# Data_Acquisition.net
KiCad netlist of a schematic drawn in EAGLE
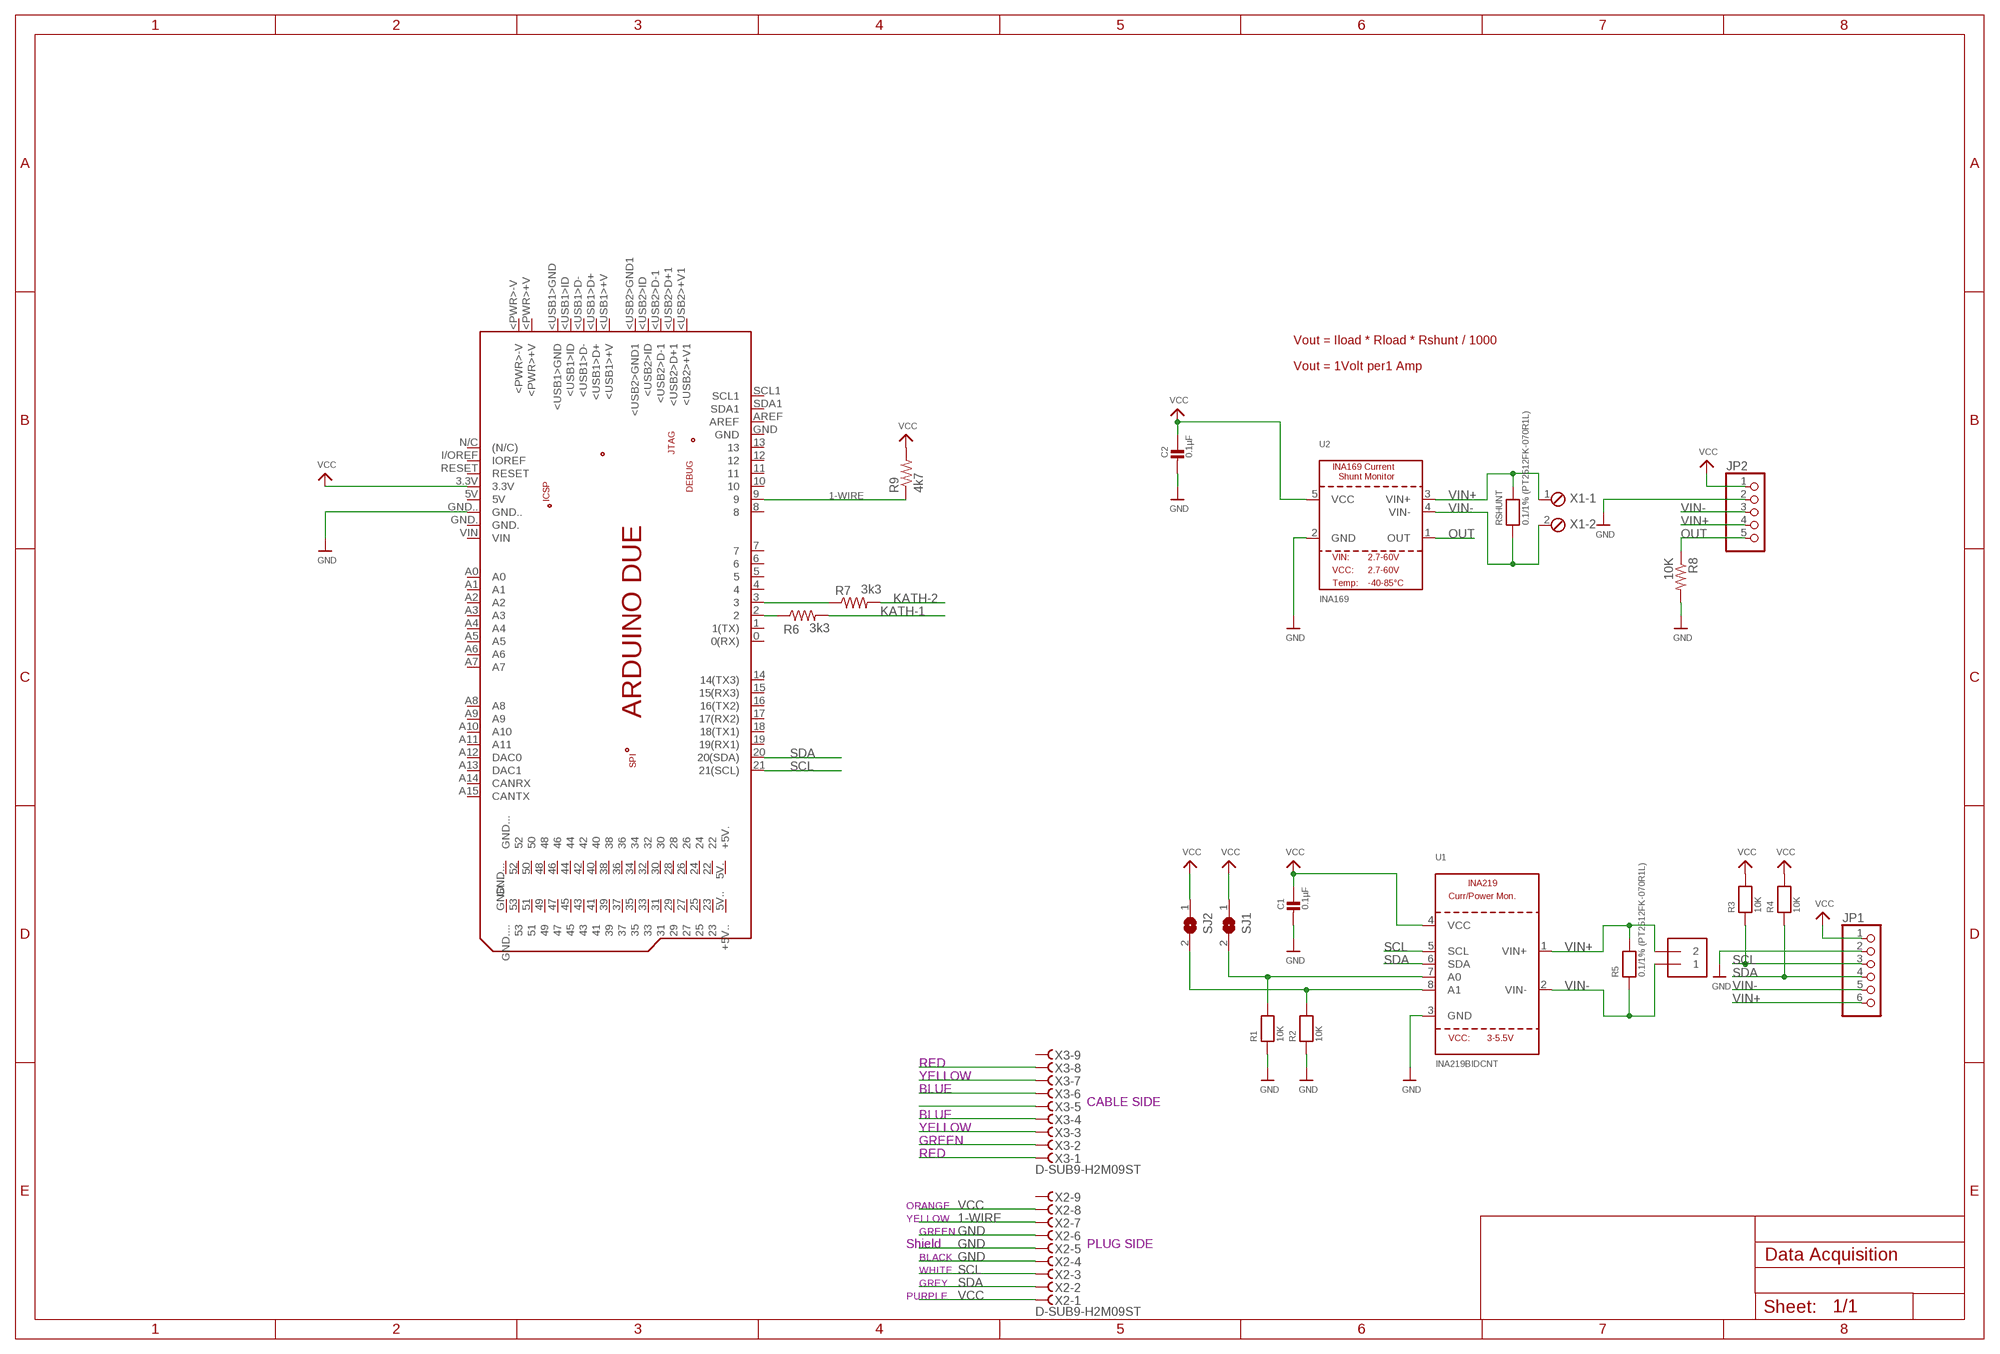
[diagram p0: schematic, sheet 1]

(export (version "E")
  (design (tool "Eeschema 10.0.6"))
  (components
    (comp (ref "C1")
      (value "0.1µF")
      (footprint "eagle-import:0805")
      (libsource (lib "eagle-import") (part "CAP_CERAMIC0805"))
    )
    (comp (ref "C2")
      (value "0.1µF")
      (footprint "eagle-import:0805")
      (libsource (lib "eagle-import") (part "CAP_CERAMIC0805"))
    )
    (comp (ref "J1")
      (value "TERMBLOCK_1X2-3.5MM")
      (footprint "eagle-import:1X2-3.5MM")
      (libsource (lib "eagle-import") (part "TERMBLOCK_1X2-3.5MM"))
    )
    (comp (ref "JP1")
      (value "HEADER-1X670MIL")
      (footprint "eagle-import:1X06_ROUND_70")
      (libsource (lib "eagle-import") (part "HEADER-1X670MIL"))
    )
    (comp (ref "JP2")
      (value "HEADER-1X570MIL")
      (footprint "eagle-import:1X05_ROUND_70")
      (libsource (lib "eagle-import") (part "HEADER-1X570MIL"))
    )
    (comp (ref "PCB1")
      (value "ARDUINO_DUE")
      (footprint "eagle-import:ARDUINO_DUE")
      (libsource (lib "eagle-import") (part "ARDUINO_DUE"))
    )
    (comp (ref "R1")
      (value "10K")
      (footprint "eagle-import:0805")
      (libsource (lib "eagle-import") (part "RESISTOR0805"))
    )
    (comp (ref "R2")
      (value "10K")
      (footprint "eagle-import:0805")
      (libsource (lib "eagle-import") (part "RESISTOR0805"))
    )
    (comp (ref "R3")
      (value "10K")
      (footprint "eagle-import:0805")
      (libsource (lib "eagle-import") (part "RESISTOR0805"))
    )
    (comp (ref "R4")
      (value "10K")
      (footprint "eagle-import:0805")
      (libsource (lib "eagle-import") (part "RESISTOR0805"))
    )
    (comp (ref "R5")
      (value "0.1/1% (PT2512FK-070R1L)")
      (footprint "eagle-import:2512")
      (libsource (lib "eagle-import") (part "RESISTOR2512"))
    )
    (comp (ref "R6")
      (value "3k3")
      (footprint "eagle-import:0204_7")
      (libsource (lib "eagle-import") (part "R-US_0204/7"))
    )
    (comp (ref "R7")
      (value "3k3")
      (footprint "eagle-import:0204_7")
      (libsource (lib "eagle-import") (part "R-US_0204/7"))
    )
    (comp (ref "R8")
      (value "10K")
      (footprint "eagle-import:0805-THM")
      (libsource (lib "eagle-import") (part "RESISTOR_DUAL"))
    )
    (comp (ref "R9")
      (value "4k7")
      (footprint "eagle-import:0207_10")
      (libsource (lib "eagle-import") (part "rcl_334_R-US_0207/10"))
    )
    (comp (ref "RSHUNT")
      (value "0.1/1% (PT2512FK-070R1L)")
      (footprint "eagle-import:2512")
      (libsource (lib "eagle-import") (part "RESISTOR2512"))
    )
    (comp (ref "SJ1")
      (value "SOLDERJUMPERREFLOW_NOPASTE")
      (footprint "eagle-import:SOLDERJUMPER_REFLOW_NOPASTE")
      (libsource (lib "eagle-import") (part "SOLDERJUMPERREFLOW_NOPASTE"))
    )
    (comp (ref "SJ2")
      (value "SOLDERJUMPERREFLOW_NOPASTE")
      (footprint "eagle-import:SOLDERJUMPER_REFLOW_NOPASTE")
      (libsource (lib "eagle-import") (part "SOLDERJUMPERREFLOW_NOPASTE"))
    )
    (comp (ref "U1")
      (value "INA219BIDCNT")
      (footprint "eagle-import:SOT23-8")
      (libsource (lib "eagle-import") (part "INA219"))
    )
    (comp (ref "U2")
      (value "INA169")
      (footprint "eagle-import:SOT23-5")
      (libsource (lib "eagle-import") (part "INA169"))
    )
    (comp (ref "X1")
      (value "MPT2")
      (footprint "eagle-import:2POL254")
      (libsource (lib "eagle-import") (part "MPT2"))
    )
    (comp (ref "X2")
      (value "D-SUB9-H2M09ST")
      (footprint "eagle-import:H2M09ST")
      (libsource (lib "eagle-import") (part "D-SUB9-H2M09ST"))
    )
    (comp (ref "X3")
      (value "D-SUB9-H2M09ST")
      (footprint "eagle-import:H2M09ST")
      (libsource (lib "eagle-import") (part "D-SUB9-H2M09ST"))
    )
  )
  (nets
    (net (code "1") (name "/1-WIRE") (class "Default")
      (node (ref "PCB1") (pin "9") (pinfunction "9_9") (pintype "bidirectional"))
      (node (ref "R9") (pin "1") (pinfunction "1_1") (pintype "passive"))
      (node (ref "X2") (pin "7") (pinfunction "F_7") (pintype "passive"))
    )
    (net (code "2") (name "/KATH-1") (class "Default")
      (node (ref "R6") (pin "2") (pinfunction "2_2") (pintype "passive"))
    )
    (net (code "3") (name "/KATH-2") (class "Default")
      (node (ref "R7") (pin "2") (pinfunction "2_2") (pintype "passive"))
    )
    (net (code "4") (name "/OUT") (class "Default")
      (node (ref "JP2") (pin "5") (pinfunction "5_5") (pintype "passive"))
      (node (ref "R8") (pin "1") (pinfunction "1_1") (pintype "passive"))
      (node (ref "U2") (pin "1") (pinfunction "OUT_1") (pintype "output"))
    )
    (net (code "5") (name "/SCL") (class "Default")
      (node (ref "JP1") (pin "3") (pinfunction "3_3") (pintype "passive"))
      (node (ref "PCB1") (pin "21") (pinfunction "21(SCL)_21") (pintype "bidirectional"))
      (node (ref "R3") (pin "1") (pinfunction "1_1") (pintype "passive"))
      (node (ref "U1") (pin "5") (pinfunction "SCL_5") (pintype "bidirectional"))
      (node (ref "X2") (pin "3") (pinfunction "F_3") (pintype "passive"))
    )
    (net (code "6") (name "/SDA") (class "Default")
      (node (ref "JP1") (pin "4") (pinfunction "4_4") (pintype "passive"))
      (node (ref "PCB1") (pin "20") (pinfunction "20(SDA)_20") (pintype "bidirectional"))
      (node (ref "R4") (pin "1") (pinfunction "1_1") (pintype "passive"))
      (node (ref "U1") (pin "6") (pinfunction "SDA_6") (pintype "bidirectional"))
      (node (ref "X2") (pin "2") (pinfunction "F_2") (pintype "passive"))
    )
    (net (code "7") (name "/VIN+") (class "Default")
      (node (ref "J1") (pin "2") (pinfunction "2_2") (pintype "passive"))
      (node (ref "JP1") (pin "6") (pinfunction "6_6") (pintype "passive"))
      (node (ref "JP2") (pin "4") (pinfunction "4_4") (pintype "passive"))
      (node (ref "R5") (pin "2") (pinfunction "2_2") (pintype "passive"))
      (node (ref "RSHUNT") (pin "2") (pinfunction "2_2") (pintype "passive"))
      (node (ref "U1") (pin "1") (pinfunction "VIN+_1") (pintype "bidirectional"))
      (node (ref "U2") (pin "3") (pinfunction "VIN+_3") (pintype "bidirectional"))
      (node (ref "X1") (pin "1") (pinfunction "1_1") (pintype "passive"))
    )
    (net (code "8") (name "/VIN-") (class "Default")
      (node (ref "J1") (pin "1") (pinfunction "1_1") (pintype "passive"))
      (node (ref "JP1") (pin "5") (pinfunction "5_5") (pintype "passive"))
      (node (ref "JP2") (pin "3") (pinfunction "3_3") (pintype "passive"))
      (node (ref "R5") (pin "1") (pinfunction "1_1") (pintype "passive"))
      (node (ref "RSHUNT") (pin "1") (pinfunction "1_1") (pintype "passive"))
      (node (ref "U1") (pin "2") (pinfunction "VIN-_2") (pintype "bidirectional"))
      (node (ref "U2") (pin "4") (pinfunction "VIN-_4") (pintype "bidirectional"))
      (node (ref "X1") (pin "2") (pinfunction "1_2") (pintype "passive"))
    )
    (net (code "9") (name "GND") (class "Default")
      (node (ref "C1") (pin "2") (pinfunction "2_2") (pintype "passive"))
      (node (ref "C2") (pin "2") (pinfunction "2_2") (pintype "passive"))
      (node (ref "JP1") (pin "2") (pinfunction "2_2") (pintype "passive"))
      (node (ref "JP2") (pin "2") (pinfunction "2_2") (pintype "passive"))
      (node (ref "PCB1") (pin "GND..") (pinfunction "GND.._GND..") (pintype "bidirectional"))
      (node (ref "R1") (pin "1") (pinfunction "1_1") (pintype "passive"))
      (node (ref "R2") (pin "1") (pinfunction "1_1") (pintype "passive"))
      (node (ref "R8") (pin "2") (pinfunction "2_2") (pintype "passive"))
      (node (ref "U1") (pin "3") (pinfunction "GND_3") (pintype "bidirectional"))
      (node (ref "U2") (pin "2") (pinfunction "GND_2") (pintype "power_in"))
      (node (ref "X2") (pin "4") (pinfunction "F_4") (pintype "passive"))
      (node (ref "X2") (pin "5") (pinfunction "F_5") (pintype "passive"))
      (node (ref "X2") (pin "6") (pinfunction "F_6") (pintype "passive"))
    )
    (net (code "10") (name "Net-(PCB1-Pad2)") (class "Default")
      (node (ref "PCB1") (pin "2") (pinfunction "2_2") (pintype "bidirectional"))
      (node (ref "R6") (pin "1") (pinfunction "1_1") (pintype "passive"))
    )
    (net (code "11") (name "Net-(PCB1-Pad3)") (class "Default")
      (node (ref "PCB1") (pin "3") (pinfunction "3_3") (pintype "bidirectional"))
      (node (ref "R7") (pin "1") (pinfunction "1_1") (pintype "passive"))
    )
    (net (code "12") (name "Net-(U1-A0)") (class "Default")
      (node (ref "R1") (pin "2") (pinfunction "2_2") (pintype "passive"))
      (node (ref "SJ1") (pin "2") (pinfunction "2_2") (pintype "passive"))
      (node (ref "U1") (pin "7") (pinfunction "A0_7") (pintype "bidirectional"))
    )
    (net (code "13") (name "Net-(U1-A1)") (class "Default")
      (node (ref "R2") (pin "2") (pinfunction "2_2") (pintype "passive"))
      (node (ref "SJ2") (pin "2") (pinfunction "2_2") (pintype "passive"))
      (node (ref "U1") (pin "8") (pinfunction "A1_8") (pintype "bidirectional"))
    )
    (net (code "14") (name "VCC") (class "Default")
      (node (ref "C1") (pin "1") (pinfunction "1_1") (pintype "passive"))
      (node (ref "C2") (pin "1") (pinfunction "1_1") (pintype "passive"))
      (node (ref "JP1") (pin "1") (pinfunction "1_1") (pintype "passive"))
      (node (ref "JP2") (pin "1") (pinfunction "1_1") (pintype "passive"))
      (node (ref "PCB1") (pin "3.3V") (pinfunction "3.3V_3.3V") (pintype "bidirectional"))
      (node (ref "R3") (pin "2") (pinfunction "2_2") (pintype "passive"))
      (node (ref "R4") (pin "2") (pinfunction "2_2") (pintype "passive"))
      (node (ref "R9") (pin "2") (pinfunction "2_2") (pintype "passive"))
      (node (ref "SJ1") (pin "1") (pinfunction "1_1") (pintype "passive"))
      (node (ref "SJ2") (pin "1") (pinfunction "1_1") (pintype "passive"))
      (node (ref "U1") (pin "4") (pinfunction "VCC_4") (pintype "bidirectional"))
      (node (ref "U2") (pin "5") (pinfunction "VCC_5") (pintype "power_in"))
      (node (ref "X2") (pin "1") (pinfunction "F_1") (pintype "passive"))
      (node (ref "X2") (pin "8") (pinfunction "F_8") (pintype "passive"))
    )
    (net (code "15") (name "unconnected-(PCB1-(N{slash}C)-PadN{slash}C)") (class "Default")
      (node (ref "PCB1") (pin "N/C") (pinfunction "(N/C)_N/C") (pintype "bidirectional"))
    )
    (net (code "16") (name "unconnected-(PCB1-+5V.-Pad5V.)") (class "Default")
      (node (ref "PCB1") (pin "5V.") (pinfunction "+5V._5V.") (pintype "bidirectional"))
    )
    (net (code "17") (name "unconnected-(PCB1-+5V..-Pad5V..)") (class "Default")
      (node (ref "PCB1") (pin "5V..") (pinfunction "+5V.._5V..") (pintype "bidirectional"))
    )
    (net (code "18") (name "unconnected-(PCB1-0(RX)-Pad0)") (class "Default")
      (node (ref "PCB1") (pin "0") (pinfunction "0(RX)_0") (pintype "bidirectional"))
    )
    (net (code "19") (name "unconnected-(PCB1-1(TX)-Pad1)") (class "Default")
      (node (ref "PCB1") (pin "1") (pinfunction "1(TX)_1") (pintype "bidirectional"))
    )
    (net (code "20") (name "unconnected-(PCB1-14(TX3)-Pad14)") (class "Default")
      (node (ref "PCB1") (pin "14") (pinfunction "14(TX3)_14") (pintype "bidirectional"))
    )
    (net (code "21") (name "unconnected-(PCB1-15(RX3)-Pad15)") (class "Default")
      (node (ref "PCB1") (pin "15") (pinfunction "15(RX3)_15") (pintype "bidirectional"))
    )
    (net (code "22") (name "unconnected-(PCB1-16(TX2)-Pad16)") (class "Default")
      (node (ref "PCB1") (pin "16") (pinfunction "16(TX2)_16") (pintype "bidirectional"))
    )
    (net (code "23") (name "unconnected-(PCB1-17(RX2)-Pad17)") (class "Default")
      (node (ref "PCB1") (pin "17") (pinfunction "17(RX2)_17") (pintype "bidirectional"))
    )
    (net (code "24") (name "unconnected-(PCB1-18(TX1)-Pad18)") (class "Default")
      (node (ref "PCB1") (pin "18") (pinfunction "18(TX1)_18") (pintype "bidirectional"))
    )
    (net (code "25") (name "unconnected-(PCB1-19(RX1)-Pad19)") (class "Default")
      (node (ref "PCB1") (pin "19") (pinfunction "19(RX1)_19") (pintype "bidirectional"))
    )
    (net (code "26") (name "unconnected-(PCB1-CANRX-PadA14)") (class "Default")
      (node (ref "PCB1") (pin "A14") (pinfunction "CANRX_A14") (pintype "bidirectional"))
    )
    (net (code "27") (name "unconnected-(PCB1-CANTX-PadA15)") (class "Default")
      (node (ref "PCB1") (pin "A15") (pinfunction "CANTX_A15") (pintype "bidirectional"))
    )
    (net (code "28") (name "unconnected-(PCB1-DAC0-PadA12)") (class "Default")
      (node (ref "PCB1") (pin "A12") (pinfunction "DAC0_A12") (pintype "bidirectional"))
    )
    (net (code "29") (name "unconnected-(PCB1-DAC1-PadA13)") (class "Default")
      (node (ref "PCB1") (pin "A13") (pinfunction "DAC1_A13") (pintype "bidirectional"))
    )
    (net (code "30") (name "unconnected-(PCB1-IOREF-PadI{slash}OREF)") (class "Default")
      (node (ref "PCB1") (pin "I/OREF") (pinfunction "IOREF_I/OREF") (pintype "bidirectional"))
    )
    (net (code "31") (name "unconnected-(PCB1-Pad+3.3V)") (class "Default")
      (node (ref "PCB1") (pin "+3.3V") (pinfunction "+3.3V_+3.3V") (pintype "bidirectional"))
    )
    (net (code "32") (name "unconnected-(PCB1-Pad+5V)") (class "Default")
      (node (ref "PCB1") (pin "+5V") (pinfunction "+5V_+5V") (pintype "bidirectional"))
    )
    (net (code "33") (name "unconnected-(PCB1-Pad+5V_)") (class "Default")
      (node (ref "PCB1") (pin "+5V_") (pinfunction "+5V__+5V_") (pintype "bidirectional"))
    )
    (net (code "34") (name "unconnected-(PCB1-Pad4)") (class "Default")
      (node (ref "PCB1") (pin "4") (pinfunction "4_4") (pintype "bidirectional"))
    )
    (net (code "35") (name "unconnected-(PCB1-Pad5)") (class "Default")
      (node (ref "PCB1") (pin "5") (pinfunction "5_5") (pintype "bidirectional"))
    )
    (net (code "36") (name "unconnected-(PCB1-Pad5V)") (class "Default")
      (node (ref "PCB1") (pin "5V") (pinfunction "5V_5V") (pintype "bidirectional"))
    )
    (net (code "37") (name "unconnected-(PCB1-Pad6)") (class "Default")
      (node (ref "PCB1") (pin "6") (pinfunction "6_6") (pintype "bidirectional"))
    )
    (net (code "38") (name "unconnected-(PCB1-Pad7)") (class "Default")
      (node (ref "PCB1") (pin "7") (pinfunction "7_7") (pintype "bidirectional"))
    )
    (net (code "39") (name "unconnected-(PCB1-Pad8)") (class "Default")
      (node (ref "PCB1") (pin "8") (pinfunction "8_8") (pintype "bidirectional"))
    )
    (net (code "40") (name "unconnected-(PCB1-Pad10)") (class "Default")
      (node (ref "PCB1") (pin "10") (pinfunction "10_10") (pintype "bidirectional"))
    )
    (net (code "41") (name "unconnected-(PCB1-Pad11)") (class "Default")
      (node (ref "PCB1") (pin "11") (pinfunction "11_11") (pintype "bidirectional"))
    )
    (net (code "42") (name "unconnected-(PCB1-Pad12)") (class "Default")
      (node (ref "PCB1") (pin "12") (pinfunction "12_12") (pintype "bidirectional"))
    )
    (net (code "43") (name "unconnected-(PCB1-Pad13)") (class "Default")
      (node (ref "PCB1") (pin "13") (pinfunction "13_13") (pintype "bidirectional"))
    )
    (net (code "44") (name "unconnected-(PCB1-Pad22)") (class "Default")
      (node (ref "PCB1") (pin "22") (pinfunction "22_22") (pintype "bidirectional"))
    )
    (net (code "45") (name "unconnected-(PCB1-Pad23)") (class "Default")
      (node (ref "PCB1") (pin "23") (pinfunction "23_23") (pintype "bidirectional"))
    )
    (net (code "46") (name "unconnected-(PCB1-Pad24)") (class "Default")
      (node (ref "PCB1") (pin "24") (pinfunction "24_24") (pintype "bidirectional"))
    )
    (net (code "47") (name "unconnected-(PCB1-Pad25)") (class "Default")
      (node (ref "PCB1") (pin "25") (pinfunction "25_25") (pintype "bidirectional"))
    )
    (net (code "48") (name "unconnected-(PCB1-Pad26)") (class "Default")
      (node (ref "PCB1") (pin "26") (pinfunction "26_26") (pintype "bidirectional"))
    )
    (net (code "49") (name "unconnected-(PCB1-Pad27)") (class "Default")
      (node (ref "PCB1") (pin "27") (pinfunction "27_27") (pintype "bidirectional"))
    )
    (net (code "50") (name "unconnected-(PCB1-Pad28)") (class "Default")
      (node (ref "PCB1") (pin "28") (pinfunction "28_28") (pintype "bidirectional"))
    )
    (net (code "51") (name "unconnected-(PCB1-Pad29)") (class "Default")
      (node (ref "PCB1") (pin "29") (pinfunction "29_29") (pintype "bidirectional"))
    )
    (net (code "52") (name "unconnected-(PCB1-Pad30)") (class "Default")
      (node (ref "PCB1") (pin "30") (pinfunction "30_30") (pintype "bidirectional"))
    )
    (net (code "53") (name "unconnected-(PCB1-Pad31)") (class "Default")
      (node (ref "PCB1") (pin "31") (pinfunction "31_31") (pintype "bidirectional"))
    )
    (net (code "54") (name "unconnected-(PCB1-Pad32)") (class "Default")
      (node (ref "PCB1") (pin "32") (pinfunction "32_32") (pintype "bidirectional"))
    )
    (net (code "55") (name "unconnected-(PCB1-Pad33)") (class "Default")
      (node (ref "PCB1") (pin "33") (pinfunction "33_33") (pintype "bidirectional"))
    )
    (net (code "56") (name "unconnected-(PCB1-Pad34)") (class "Default")
      (node (ref "PCB1") (pin "34") (pinfunction "34_34") (pintype "bidirectional"))
    )
    (net (code "57") (name "unconnected-(PCB1-Pad35)") (class "Default")
      (node (ref "PCB1") (pin "35") (pinfunction "35_35") (pintype "bidirectional"))
    )
    (net (code "58") (name "unconnected-(PCB1-Pad36)") (class "Default")
      (node (ref "PCB1") (pin "36") (pinfunction "36_36") (pintype "bidirectional"))
    )
    (net (code "59") (name "unconnected-(PCB1-Pad37)") (class "Default")
      (node (ref "PCB1") (pin "37") (pinfunction "37_37") (pintype "bidirectional"))
    )
    (net (code "60") (name "unconnected-(PCB1-Pad38)") (class "Default")
      (node (ref "PCB1") (pin "38") (pinfunction "38_38") (pintype "bidirectional"))
    )
    (net (code "61") (name "unconnected-(PCB1-Pad39)") (class "Default")
      (node (ref "PCB1") (pin "39") (pinfunction "39_39") (pintype "bidirectional"))
    )
    (net (code "62") (name "unconnected-(PCB1-Pad40)") (class "Default")
      (node (ref "PCB1") (pin "40") (pinfunction "40_40") (pintype "bidirectional"))
    )
    (net (code "63") (name "unconnected-(PCB1-Pad41)") (class "Default")
      (node (ref "PCB1") (pin "41") (pinfunction "41_41") (pintype "bidirectional"))
    )
    (net (code "64") (name "unconnected-(PCB1-Pad42)") (class "Default")
      (node (ref "PCB1") (pin "42") (pinfunction "42_42") (pintype "bidirectional"))
    )
    (net (code "65") (name "unconnected-(PCB1-Pad43)") (class "Default")
      (node (ref "PCB1") (pin "43") (pinfunction "43_43") (pintype "bidirectional"))
    )
    (net (code "66") (name "unconnected-(PCB1-Pad44)") (class "Default")
      (node (ref "PCB1") (pin "44") (pinfunction "44_44") (pintype "bidirectional"))
    )
    (net (code "67") (name "unconnected-(PCB1-Pad45)") (class "Default")
      (node (ref "PCB1") (pin "45") (pinfunction "45_45") (pintype "bidirectional"))
    )
    (net (code "68") (name "unconnected-(PCB1-Pad46)") (class "Default")
      (node (ref "PCB1") (pin "46") (pinfunction "46_46") (pintype "bidirectional"))
    )
    (net (code "69") (name "unconnected-(PCB1-Pad47)") (class "Default")
      (node (ref "PCB1") (pin "47") (pinfunction "47_47") (pintype "bidirectional"))
    )
    (net (code "70") (name "unconnected-(PCB1-Pad48)") (class "Default")
      (node (ref "PCB1") (pin "48") (pinfunction "48_48") (pintype "bidirectional"))
    )
    (net (code "71") (name "unconnected-(PCB1-Pad49)") (class "Default")
      (node (ref "PCB1") (pin "49") (pinfunction "49_49") (pintype "bidirectional"))
    )
    (net (code "72") (name "unconnected-(PCB1-Pad50)") (class "Default")
      (node (ref "PCB1") (pin "50") (pinfunction "50_50") (pintype "bidirectional"))
    )
    (net (code "73") (name "unconnected-(PCB1-Pad51)") (class "Default")
      (node (ref "PCB1") (pin "51") (pinfunction "51_51") (pintype "bidirectional"))
    )
    (net (code "74") (name "unconnected-(PCB1-Pad52)") (class "Default")
      (node (ref "PCB1") (pin "52") (pinfunction "52_52") (pintype "bidirectional"))
    )
    (net (code "75") (name "unconnected-(PCB1-Pad53)") (class "Default")
      (node (ref "PCB1") (pin "53") (pinfunction "53_53") (pintype "bidirectional"))
    )
    (net (code "76") (name "unconnected-(PCB1-Pad<PWR>+V)") (class "Default")
      (node (ref "PCB1") (pin "<PWR>+V") (pinfunction "<PWR>+V_<PWR>+V") (pintype "bidirectional"))
    )
    (net (code "77") (name "unconnected-(PCB1-Pad<PWR>-V)") (class "Default")
      (node (ref "PCB1") (pin "<PWR>-V") (pinfunction "<PWR>-V_<PWR>-V") (pintype "bidirectional"))
    )
    (net (code "78") (name "unconnected-(PCB1-Pad<USB1>+V)") (class "Default")
      (node (ref "PCB1") (pin "<USB1>+V") (pinfunction "<USB1>+V_<USB1>+V") (pintype "bidirectional"))
    )
    (net (code "79") (name "unconnected-(PCB1-Pad<USB1>D+)") (class "Default")
      (node (ref "PCB1") (pin "<USB1>D+") (pinfunction "<USB1>D+_<USB1>D+") (pintype "bidirectional"))
    )
    (net (code "80") (name "unconnected-(PCB1-Pad<USB1>D-)") (class "Default")
      (node (ref "PCB1") (pin "<USB1>D-") (pinfunction "<USB1>D-_<USB1>D-") (pintype "bidirectional"))
    )
    (net (code "81") (name "unconnected-(PCB1-Pad<USB1>GND)") (class "Default")
      (node (ref "PCB1") (pin "<USB1>GND") (pinfunction "<USB1>GND_<USB1>GND") (pintype "bidirectional"))
    )
    (net (code "82") (name "unconnected-(PCB1-Pad<USB1>ID)") (class "Default")
      (node (ref "PCB1") (pin "<USB1>ID") (pinfunction "<USB1>ID_<USB1>ID") (pintype "bidirectional"))
    )
    (net (code "83") (name "unconnected-(PCB1-Pad<USB2>+V1)") (class "Default")
      (node (ref "PCB1") (pin "<USB2>+V1") (pinfunction "<USB2>+V1_<USB2>+V1") (pintype "bidirectional"))
    )
    (net (code "84") (name "unconnected-(PCB1-Pad<USB2>D+1)") (class "Default")
      (node (ref "PCB1") (pin "<USB2>D+1") (pinfunction "<USB2>D+1_<USB2>D+1") (pintype "bidirectional"))
    )
    (net (code "85") (name "unconnected-(PCB1-Pad<USB2>D-1)") (class "Default")
      (node (ref "PCB1") (pin "<USB2>D-1") (pinfunction "<USB2>D-1_<USB2>D-1") (pintype "bidirectional"))
    )
    (net (code "86") (name "unconnected-(PCB1-Pad<USB2>GND1)") (class "Default")
      (node (ref "PCB1") (pin "<USB2>GND1") (pinfunction "<USB2>GND1_<USB2>GND1") (pintype "bidirectional"))
    )
    (net (code "87") (name "unconnected-(PCB1-Pad<USB2>ID)") (class "Default")
      (node (ref "PCB1") (pin "<USB2>ID") (pinfunction "<USB2>ID_<USB2>ID") (pintype "bidirectional"))
    )
    (net (code "88") (name "unconnected-(PCB1-PadA0)") (class "Default")
      (node (ref "PCB1") (pin "A0") (pinfunction "A0_A0") (pintype "bidirectional"))
    )
    (net (code "89") (name "unconnected-(PCB1-PadA1)") (class "Default")
      (node (ref "PCB1") (pin "A1") (pinfunction "A1_A1") (pintype "bidirectional"))
    )
    (net (code "90") (name "unconnected-(PCB1-PadA2)") (class "Default")
      (node (ref "PCB1") (pin "A2") (pinfunction "A2_A2") (pintype "bidirectional"))
    )
    (net (code "91") (name "unconnected-(PCB1-PadA3)") (class "Default")
      (node (ref "PCB1") (pin "A3") (pinfunction "A3_A3") (pintype "bidirectional"))
    )
    (net (code "92") (name "unconnected-(PCB1-PadA4)") (class "Default")
      (node (ref "PCB1") (pin "A4") (pinfunction "A4_A4") (pintype "bidirectional"))
    )
    (net (code "93") (name "unconnected-(PCB1-PadA5)") (class "Default")
      (node (ref "PCB1") (pin "A5") (pinfunction "A5_A5") (pintype "bidirectional"))
    )
    (net (code "94") (name "unconnected-(PCB1-PadA6)") (class "Default")
      (node (ref "PCB1") (pin "A6") (pinfunction "A6_A6") (pintype "bidirectional"))
    )
    (net (code "95") (name "unconnected-(PCB1-PadA7)") (class "Default")
      (node (ref "PCB1") (pin "A7") (pinfunction "A7_A7") (pintype "bidirectional"))
    )
    (net (code "96") (name "unconnected-(PCB1-PadA8)") (class "Default")
      (node (ref "PCB1") (pin "A8") (pinfunction "A8_A8") (pintype "bidirectional"))
    )
    (net (code "97") (name "unconnected-(PCB1-PadA9)") (class "Default")
      (node (ref "PCB1") (pin "A9") (pinfunction "A9_A9") (pintype "bidirectional"))
    )
    (net (code "98") (name "unconnected-(PCB1-PadA10)") (class "Default")
      (node (ref "PCB1") (pin "A10") (pinfunction "A10_A10") (pintype "bidirectional"))
    )
    (net (code "99") (name "unconnected-(PCB1-PadA11)") (class "Default")
      (node (ref "PCB1") (pin "A11") (pinfunction "A11_A11") (pintype "bidirectional"))
    )
    (net (code "100") (name "unconnected-(PCB1-PadAREF)") (class "Default")
      (node (ref "PCB1") (pin "AREF") (pinfunction "AREF_AREF") (pintype "bidirectional"))
    )
    (net (code "101") (name "unconnected-(PCB1-PadGND)") (class "Default")
      (node (ref "PCB1") (pin "GND") (pinfunction "GND_GND") (pintype "bidirectional"))
    )
    (net (code "102") (name "unconnected-(PCB1-PadGND.)") (class "Default")
      (node (ref "PCB1") (pin "GND.") (pinfunction "GND._GND.") (pintype "bidirectional"))
    )
    (net (code "103") (name "unconnected-(PCB1-PadGND...)") (class "Default")
      (node (ref "PCB1") (pin "GND...") (pinfunction "GND..._GND...") (pintype "bidirectional"))
    )
    (net (code "104") (name "unconnected-(PCB1-PadGND....)") (class "Default")
      (node (ref "PCB1") (pin "GND....") (pinfunction "GND...._GND....") (pintype "bidirectional"))
    )
    (net (code "105") (name "unconnected-(PCB1-PadGND1)") (class "Default")
      (node (ref "PCB1") (pin "GND1") (pinfunction "GND1_GND1") (pintype "bidirectional"))
    )
    (net (code "106") (name "unconnected-(PCB1-PadGND1.)") (class "Default")
      (node (ref "PCB1") (pin "GND1.") (pinfunction "GND1._GND1.") (pintype "bidirectional"))
    )
    (net (code "107") (name "unconnected-(PCB1-PadGND1..)") (class "Default")
      (node (ref "PCB1") (pin "GND1..") (pinfunction "GND1.._GND1..") (pintype "bidirectional"))
    )
    (net (code "108") (name "unconnected-(PCB1-PadGND1...)") (class "Default")
      (node (ref "PCB1") (pin "GND1...") (pinfunction "GND1..._GND1...") (pintype "bidirectional"))
    )
    (net (code "109") (name "unconnected-(PCB1-PadGND_)") (class "Default")
      (node (ref "PCB1") (pin "GND_") (pinfunction "GND__GND_") (pintype "bidirectional"))
    )
    (net (code "110") (name "unconnected-(PCB1-PadGND__)") (class "Default")
      (node (ref "PCB1") (pin "GND__") (pinfunction "GND___GND__") (pintype "bidirectional"))
    )
    (net (code "111") (name "unconnected-(PCB1-PadMISO)") (class "Default")
      (node (ref "PCB1") (pin "MISO") (pinfunction "MISO_MISO") (pintype "bidirectional"))
    )
    (net (code "112") (name "unconnected-(PCB1-PadMISO2)") (class "Default")
      (node (ref "PCB1") (pin "MISO2") (pinfunction "MISO2_MISO2") (pintype "bidirectional"))
    )
    (net (code "113") (name "unconnected-(PCB1-PadMOSI)") (class "Default")
      (node (ref "PCB1") (pin "MOSI") (pinfunction "MOSI_MOSI") (pintype "bidirectional"))
    )
    (net (code "114") (name "unconnected-(PCB1-PadMOSI2)") (class "Default")
      (node (ref "PCB1") (pin "MOSI2") (pinfunction "MOSI2_MOSI2") (pintype "bidirectional"))
    )
    (net (code "115") (name "unconnected-(PCB1-PadN{slash}C.)") (class "Default")
      (node (ref "PCB1") (pin "N/C.") (pinfunction "N/C._N/C.") (pintype "bidirectional"))
    )
    (net (code "116") (name "unconnected-(PCB1-PadRESET)") (class "Default")
      (node (ref "PCB1") (pin "RESET") (pinfunction "RESET_RESET") (pintype "bidirectional"))
    )
    (net (code "117") (name "unconnected-(PCB1-PadRESET.)") (class "Default")
      (node (ref "PCB1") (pin "RESET.") (pinfunction "RESET._RESET.") (pintype "bidirectional"))
    )
    (net (code "118") (name "unconnected-(PCB1-PadRESET..)") (class "Default")
      (node (ref "PCB1") (pin "RESET..") (pinfunction "RESET.._RESET..") (pintype "bidirectional"))
    )
    (net (code "119") (name "unconnected-(PCB1-PadRESET2)") (class "Default")
      (node (ref "PCB1") (pin "RESET2") (pinfunction "RESET2_RESET2") (pintype "bidirectional"))
    )
    (net (code "120") (name "unconnected-(PCB1-PadRESET_)") (class "Default")
      (node (ref "PCB1") (pin "RESET_") (pinfunction "RESET__RESET_") (pintype "bidirectional"))
    )
    (net (code "121") (name "unconnected-(PCB1-PadSCK)") (class "Default")
      (node (ref "PCB1") (pin "SCK") (pinfunction "SCK_SCK") (pintype "bidirectional"))
    )
    (net (code "122") (name "unconnected-(PCB1-PadSCK2)") (class "Default")
      (node (ref "PCB1") (pin "SCK2") (pinfunction "SCK2_SCK2") (pintype "bidirectional"))
    )
    (net (code "123") (name "unconnected-(PCB1-PadSCL1)") (class "Default")
      (node (ref "PCB1") (pin "SCL1") (pinfunction "SCL1_SCL1") (pintype "bidirectional"))
    )
    (net (code "124") (name "unconnected-(PCB1-PadSDA1)") (class "Default")
      (node (ref "PCB1") (pin "SDA1") (pinfunction "SDA1_SDA1") (pintype "bidirectional"))
    )
    (net (code "125") (name "unconnected-(PCB1-PadSWCLK)") (class "Default")
      (node (ref "PCB1") (pin "SWCLK") (pinfunction "SWCLK_SWCLK") (pintype "bidirectional"))
    )
    (net (code "126") (name "unconnected-(PCB1-PadSWDIO)") (class "Default")
      (node (ref "PCB1") (pin "SWDIO") (pinfunction "SWDIO_SWDIO") (pintype "bidirectional"))
    )
    (net (code "127") (name "unconnected-(PCB1-PadTCK)") (class "Default")
      (node (ref "PCB1") (pin "TCK") (pinfunction "TCK_TCK") (pintype "bidirectional"))
    )
    (net (code "128") (name "unconnected-(PCB1-PadTDI)") (class "Default")
      (node (ref "PCB1") (pin "TDI") (pinfunction "TDI_TDI") (pintype "bidirectional"))
    )
    (net (code "129") (name "unconnected-(PCB1-PadTDO)") (class "Default")
      (node (ref "PCB1") (pin "TDO") (pinfunction "TDO_TDO") (pintype "bidirectional"))
    )
    (net (code "130") (name "unconnected-(PCB1-PadTMS)") (class "Default")
      (node (ref "PCB1") (pin "TMS") (pinfunction "TMS_TMS") (pintype "bidirectional"))
    )
    (net (code "131") (name "unconnected-(PCB1-PadVIN)") (class "Default")
      (node (ref "PCB1") (pin "VIN") (pinfunction "VIN_VIN") (pintype "bidirectional"))
    )
    (net (code "132") (name "unconnected-(X2I-F-Pad9)") (class "Default")
      (node (ref "X2") (pin "9") (pinfunction "F_9") (pintype "passive"))
    )
    (net (code "133") (name "unconnected-(X3A-F-Pad1)") (class "Default")
      (node (ref "X3") (pin "1") (pinfunction "F_1") (pintype "passive"))
    )
    (net (code "134") (name "unconnected-(X3B-F-Pad2)") (class "Default")
      (node (ref "X3") (pin "2") (pinfunction "F_2") (pintype "passive"))
    )
    (net (code "135") (name "unconnected-(X3C-F-Pad3)") (class "Default")
      (node (ref "X3") (pin "3") (pinfunction "F_3") (pintype "passive"))
    )
    (net (code "136") (name "unconnected-(X3D-F-Pad4)") (class "Default")
      (node (ref "X3") (pin "4") (pinfunction "F_4") (pintype "passive"))
    )
    (net (code "137") (name "unconnected-(X3E-F-Pad5)") (class "Default")
      (node (ref "X3") (pin "5") (pinfunction "F_5") (pintype "passive"))
    )
    (net (code "138") (name "unconnected-(X3F-F-Pad6)") (class "Default")
      (node (ref "X3") (pin "6") (pinfunction "F_6") (pintype "passive"))
    )
    (net (code "139") (name "unconnected-(X3G-F-Pad7)") (class "Default")
      (node (ref "X3") (pin "7") (pinfunction "F_7") (pintype "passive"))
    )
    (net (code "140") (name "unconnected-(X3H-F-Pad8)") (class "Default")
      (node (ref "X3") (pin "8") (pinfunction "F_8") (pintype "passive"))
    )
    (net (code "141") (name "unconnected-(X3I-F-Pad9)") (class "Default")
      (node (ref "X3") (pin "9") (pinfunction "F_9") (pintype "passive"))
    )
  )
)
